# Triple_Micro_Shield.net
KiCad netlist of a schematic drawn in EAGLE
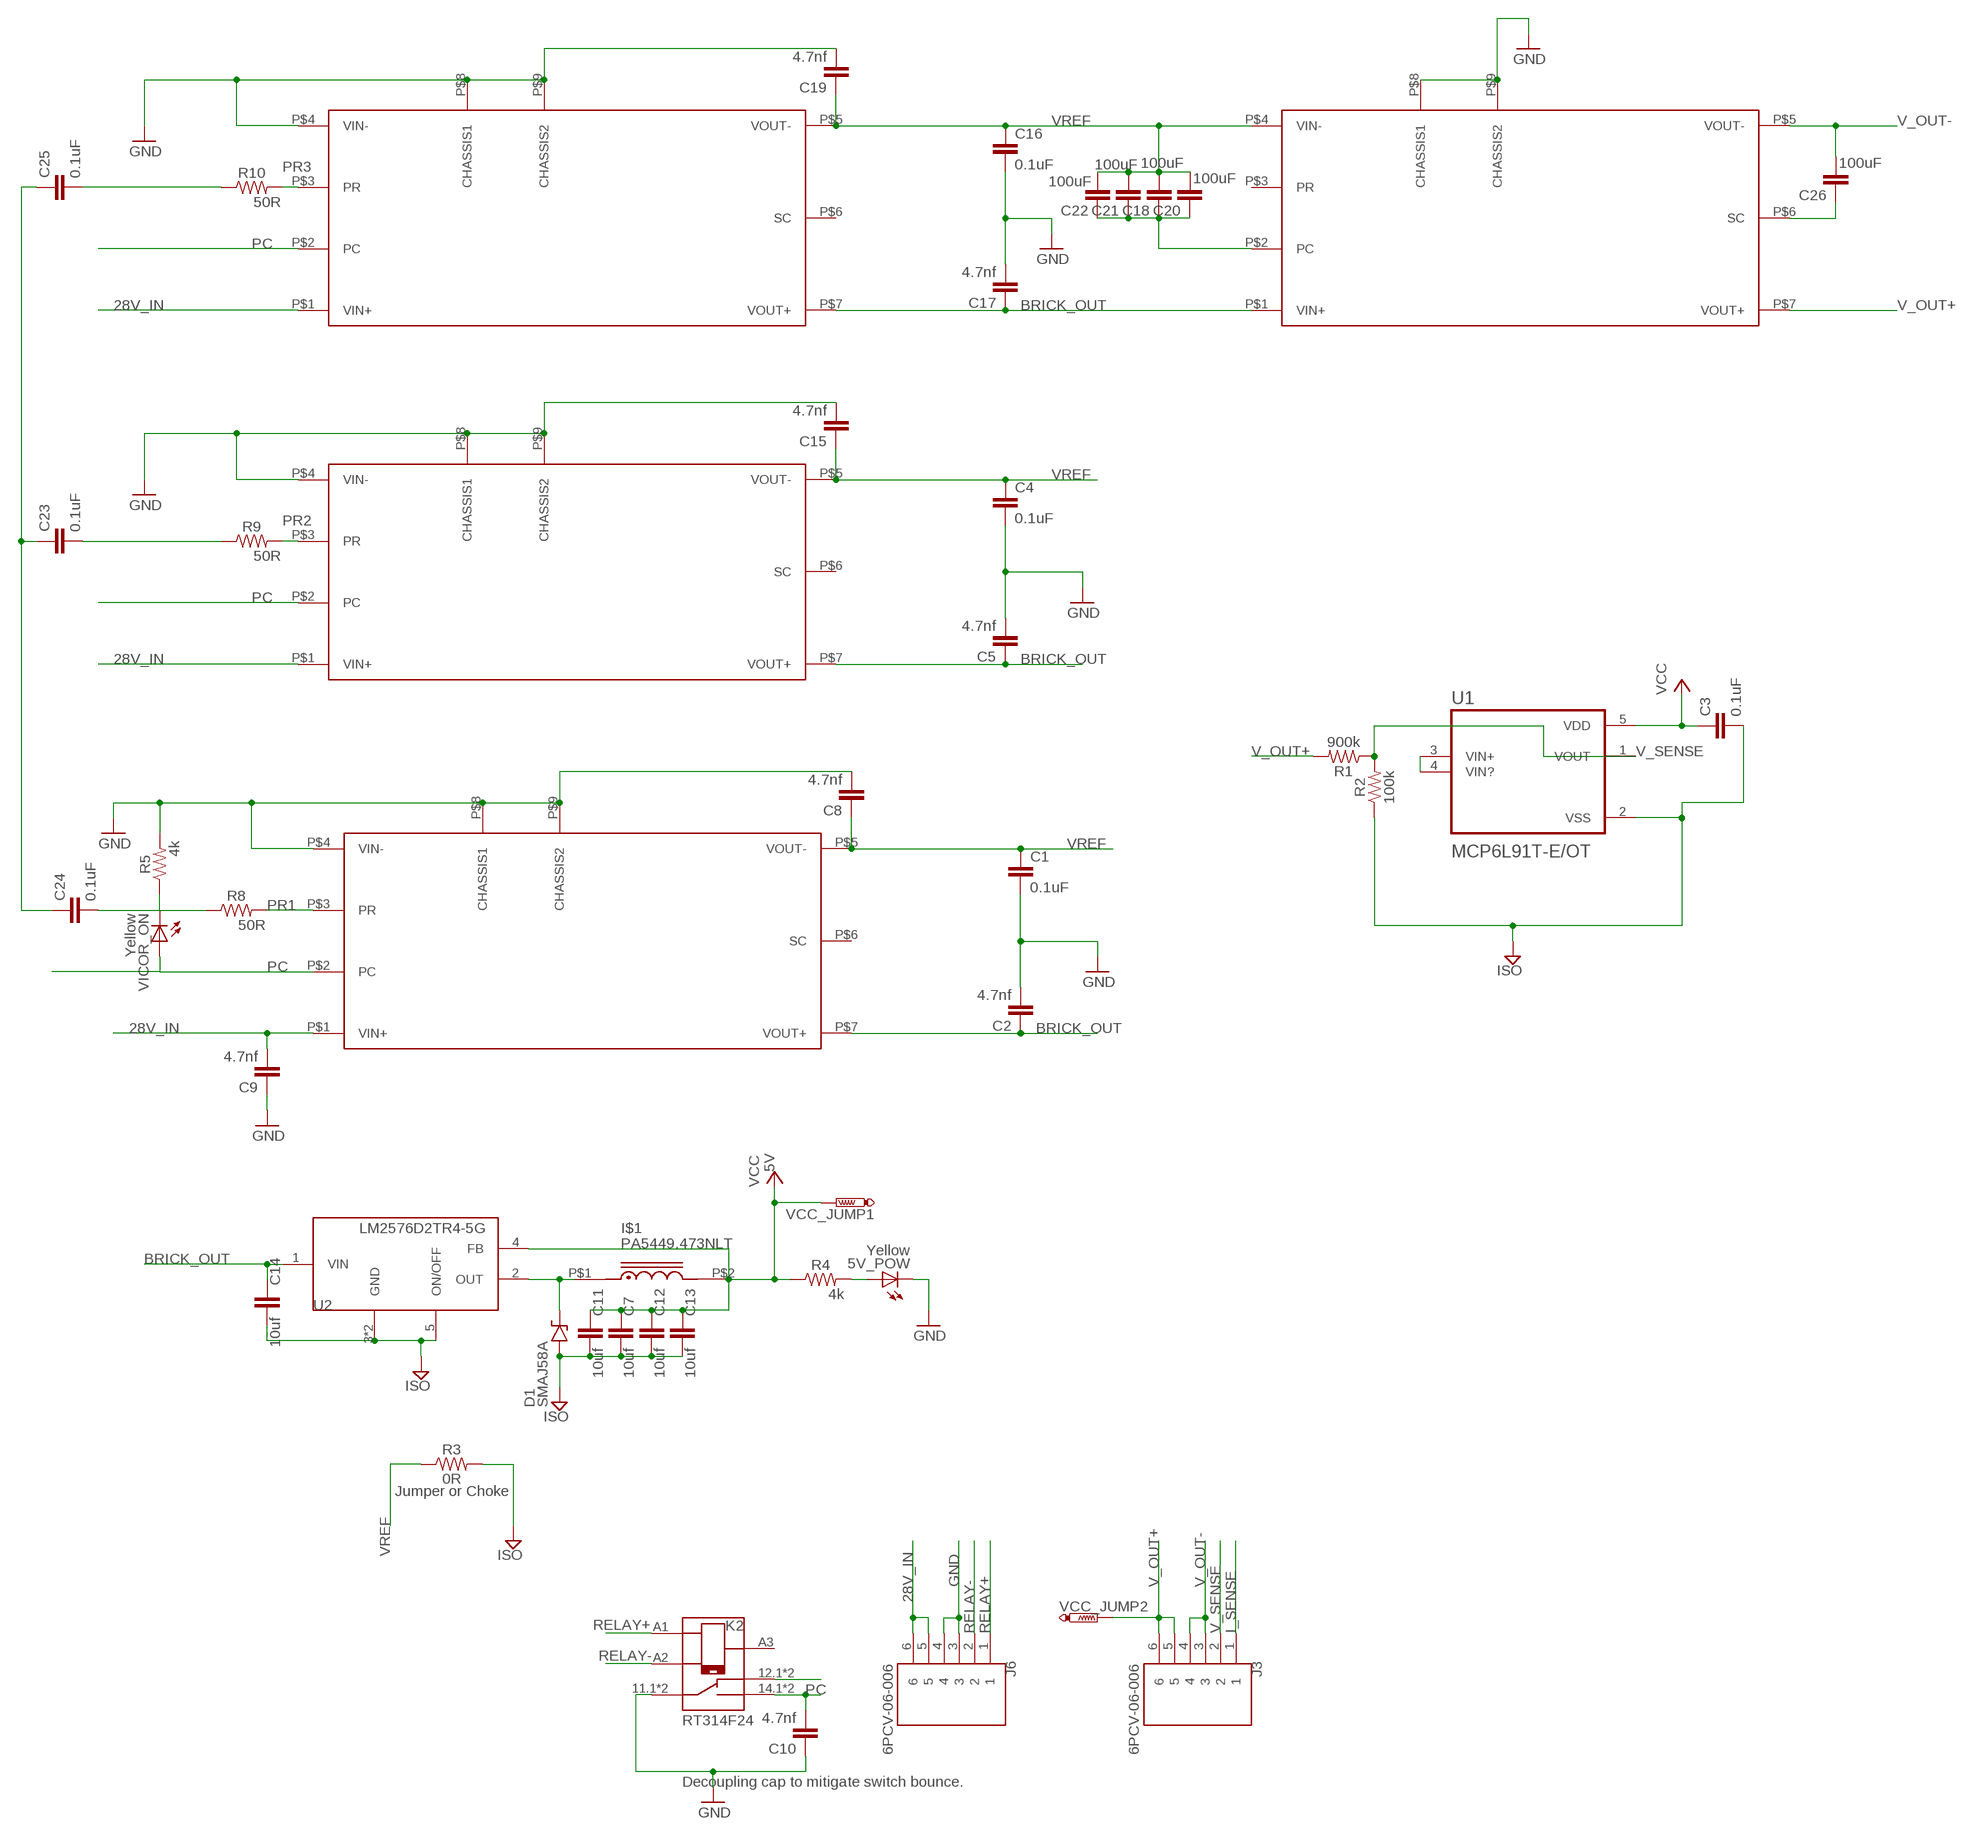
[diagram p0: schematic, sheet 1]

(export (version "E")
  (design (tool "Eeschema 10.0.6"))
  (components
    (comp (ref "5V_POW")
      (value "Yellow")
      (footprint "eagle-import:CHIPLED_0805")
      (fields (field (name "PART_NUMBER") "KPT-2012YC"))
      (libsource (lib "eagle-import") (part "0044_KPT-2012YC"))
    )
    (comp (ref "C1")
      (value "0.1uF")
      (footprint "eagle-import:0603")
      (libsource (lib "eagle-import") (part "5.6NF/5600PF_0603_50V_5%"))
    )
    (comp (ref "C2")
      (value "4.7nf")
      (footprint "eagle-import:0603")
      (libsource (lib "eagle-import") (part "5.6NF/5600PF_0603_50V_5%"))
    )
    (comp (ref "C3")
      (value "0.1uF")
      (footprint "eagle-import:0603")
      (libsource (lib "eagle-import") (part "5.6NF/5600PF_0603_50V_5%"))
    )
    (comp (ref "C4")
      (value "0.1uF")
      (footprint "eagle-import:0603")
      (libsource (lib "eagle-import") (part "5.6NF/5600PF_0603_50V_5%"))
    )
    (comp (ref "C5")
      (value "4.7nf")
      (footprint "eagle-import:0603")
      (libsource (lib "eagle-import") (part "5.6NF/5600PF_0603_50V_5%"))
    )
    (comp (ref "C7")
      (value "10uf")
      (footprint "eagle-import:0805")
      (libsource (lib "eagle-import") (part "39NF-0805-50V-10%"))
    )
    (comp (ref "C8")
      (value "4.7nf")
      (footprint "eagle-import:0603")
      (libsource (lib "eagle-import") (part "5.6NF/5600PF_0603_50V_5%"))
    )
    (comp (ref "C9")
      (value "4.7nf")
      (footprint "eagle-import:0603")
      (libsource (lib "eagle-import") (part "5.6NF/5600PF_0603_50V_5%"))
    )
    (comp (ref "C10")
      (value "4.7nf")
      (footprint "eagle-import:0603")
      (libsource (lib "eagle-import") (part "5.6NF/5600PF_0603_50V_5%"))
    )
    (comp (ref "C11")
      (value "10uf")
      (footprint "eagle-import:0805")
      (libsource (lib "eagle-import") (part "39NF-0805-50V-10%"))
    )
    (comp (ref "C12")
      (value "10uf")
      (footprint "eagle-import:0805")
      (libsource (lib "eagle-import") (part "39NF-0805-50V-10%"))
    )
    (comp (ref "C13")
      (value "10uf")
      (footprint "eagle-import:0805")
      (libsource (lib "eagle-import") (part "39NF-0805-50V-10%"))
    )
    (comp (ref "C14")
      (value "10uf")
      (footprint "eagle-import:0805")
      (libsource (lib "eagle-import") (part "39NF-0805-50V-10%"))
    )
    (comp (ref "C15")
      (value "4.7nf")
      (footprint "eagle-import:0603")
      (libsource (lib "eagle-import") (part "5.6NF/5600PF_0603_50V_5%"))
    )
    (comp (ref "C16")
      (value "0.1uF")
      (footprint "eagle-import:0603")
      (libsource (lib "eagle-import") (part "5.6NF/5600PF_0603_50V_5%"))
    )
    (comp (ref "C17")
      (value "4.7nf")
      (footprint "eagle-import:0603")
      (libsource (lib "eagle-import") (part "5.6NF/5600PF_0603_50V_5%"))
    )
    (comp (ref "C18")
      (value "100uF")
      (footprint "eagle-import:0603")
      (libsource (lib "eagle-import") (part "5.6NF/5600PF_0603_50V_5%"))
    )
    (comp (ref "C19")
      (value "4.7nf")
      (footprint "eagle-import:0603")
      (libsource (lib "eagle-import") (part "5.6NF/5600PF_0603_50V_5%"))
    )
    (comp (ref "C20")
      (value "100uF")
      (footprint "eagle-import:0603")
      (libsource (lib "eagle-import") (part "5.6NF/5600PF_0603_50V_5%"))
    )
    (comp (ref "C21")
      (value "100uF")
      (footprint "eagle-import:0603")
      (libsource (lib "eagle-import") (part "5.6NF/5600PF_0603_50V_5%"))
    )
    (comp (ref "C22")
      (value "100uF")
      (footprint "eagle-import:0603")
      (libsource (lib "eagle-import") (part "5.6NF/5600PF_0603_50V_5%"))
    )
    (comp (ref "C23")
      (value "0.1uF")
      (footprint "eagle-import:0603")
      (libsource (lib "eagle-import") (part "5.6NF/5600PF_0603_50V_5%"))
    )
    (comp (ref "C24")
      (value "0.1uF")
      (footprint "eagle-import:0603")
      (libsource (lib "eagle-import") (part "5.6NF/5600PF_0603_50V_5%"))
    )
    (comp (ref "C25")
      (value "0.1uF")
      (footprint "eagle-import:0603")
      (libsource (lib "eagle-import") (part "5.6NF/5600PF_0603_50V_5%"))
    )
    (comp (ref "C26")
      (value "100uF")
      (footprint "eagle-import:0603")
      (libsource (lib "eagle-import") (part "5.6NF/5600PF_0603_50V_5%"))
    )
    (comp (ref "D1")
      (value "SMAJ58A")
      (footprint "eagle-import:SMA")
      (fields (field (name "MF") "Littelfuse Inc."))
      (libsource (lib "eagle-import") (part "SMAJ58A"))
    )
    (comp (ref "I$1")
      (value "PA5449.473NLT")
      (footprint "eagle-import:IND_TYS4020470M-10")
      (libsource (lib "eagle-import") (part "PULSE_ELECTRONICS_INDUCTOR"))
    )
    (comp (ref "J3")
      (value "6PCV-06-006")
      (footprint "eagle-import:TE_9-1437652-5")
      (fields (field (name "COMMENT") "9-1437652-5") (field (name "MF") "TE Connectivity"))
      (libsource (lib "eagle-import") (part "6PCV-06-006"))
    )
    (comp (ref "J6")
      (value "6PCV-06-006")
      (footprint "eagle-import:TE_9-1437652-5")
      (fields (field (name "COMMENT") "9-1437652-5") (field (name "MF") "TE Connectivity"))
      (libsource (lib "eagle-import") (part "6PCV-06-006"))
    )
    (comp (ref "K2")
      (value "RT314F24")
      (footprint "eagle-import:TE_8-1393239-8")
      (fields (field (name "COMMENT") "8-1393239-8") (field (name "MF") "TE Connectivity"))
      (libsource (lib "eagle-import") (part "8-1393239-8"))
    )
    (comp (ref "R1")
      (value "900k")
      (footprint "eagle-import:0603")
      (libsource (lib "eagle-import") (part "1.8MOHM"))
    )
    (comp (ref "R2")
      (value "100k")
      (footprint "eagle-import:0603")
      (libsource (lib "eagle-import") (part "1.8MOHM"))
    )
    (comp (ref "R3")
      (value "0R")
      (footprint "eagle-import:0603")
      (libsource (lib "eagle-import") (part "1.8MOHM"))
    )
    (comp (ref "R4")
      (value "4k")
      (footprint "eagle-import:0603")
      (libsource (lib "eagle-import") (part "1.8MOHM"))
    )
    (comp (ref "R5")
      (value "4k")
      (footprint "eagle-import:0603")
      (libsource (lib "eagle-import") (part "1.8MOHM"))
    )
    (comp (ref "R8")
      (value "50R")
      (footprint "eagle-import:0603")
      (libsource (lib "eagle-import") (part "1.8MOHM"))
    )
    (comp (ref "R9")
      (value "50R")
      (footprint "eagle-import:0603")
      (libsource (lib "eagle-import") (part "1.8MOHM"))
    )
    (comp (ref "R10")
      (value "50R")
      (footprint "eagle-import:0603")
      (libsource (lib "eagle-import") (part "1.8MOHM"))
    )
    (comp (ref "U$2")
      (value "VICOR_MINI_BRICK_VICORMINIBRICK")
      (footprint "eagle-import:VICOR_MINI_BRICK_MINIBRICK")
      (libsource (lib "eagle-import") (part "VICOR_MINI_BRICK_VICORMINIBRICK"))
    )
    (comp (ref "U$3")
      (value "VICOR_MINI_BRICK_VICORMINIBRICK")
      (footprint "eagle-import:VICOR_MINI_BRICK_MINIBRICK")
      (libsource (lib "eagle-import") (part "VICOR_MINI_BRICK_VICORMINIBRICK"))
    )
    (comp (ref "U$4")
      (value "VICOR_MINI_BRICK_VICORMINIBRICK")
      (footprint "eagle-import:VICOR_MINI_BRICK_MINIBRICK")
      (libsource (lib "eagle-import") (part "VICOR_MINI_BRICK_VICORMINIBRICK"))
    )
    (comp (ref "U$5")
      (value "VICOR_MINI_BRICK_VICORMINIBRICK")
      (footprint "eagle-import:VICOR_MINI_BRICK_MINIBRICK")
      (libsource (lib "eagle-import") (part "VICOR_MINI_BRICK_VICORMINIBRICK"))
    )
    (comp (ref "U1")
      (value "MCP6L91T-E/OT")
      (footprint "eagle-import:SOT95P270X145-5N")
      (fields (field (name "MF") "Microchip Technology"))
      (libsource (lib "eagle-import") (part "MCP6L91T-E/OT"))
    )
    (comp (ref "U2")
      (value "LM2576D2TR4-5G")
      (footprint "eagle-import:D2PAK-5")
      (fields (field (name "MF") "ON Semiconductor"))
      (libsource (lib "eagle-import") (part "LM2576D2TR4-5G"))
    )
    (comp (ref "VCC_JUMP1")
      (value "PTR1PAD1-13")
      (footprint "eagle-import:P1-13")
      (libsource (lib "eagle-import") (part "PTR1PAD1-13"))
    )
    (comp (ref "VCC_JUMP2")
      (value "PTR1PAD1-13")
      (footprint "eagle-import:P1-13")
      (libsource (lib "eagle-import") (part "PTR1PAD1-13"))
    )
    (comp (ref "VICOR_ON")
      (value "Yellow")
      (footprint "eagle-import:CHIPLED_0805")
      (fields (field (name "PART_NUMBER") "KPT-2012YC"))
      (libsource (lib "eagle-import") (part "0044_KPT-2012YC"))
    )
  )
  (nets
    (net (code "1") (name "/28V_IN") (class "Default")
      (node (ref "C9") (pin "2") (pinfunction "2_2") (pintype "passive"))
      (node (ref "J6") (pin "5") (pinfunction "5_5") (pintype "passive"))
      (node (ref "J6") (pin "6") (pinfunction "6_6") (pintype "passive"))
      (node (ref "U$2") (pin "P$1") (pinfunction "VIN+_P$1") (pintype "bidirectional"))
      (node (ref "U$3") (pin "P$1") (pinfunction "VIN+_P$1") (pintype "bidirectional"))
      (node (ref "U$4") (pin "P$1") (pinfunction "VIN+_P$1") (pintype "bidirectional"))
    )
    (net (code "2") (name "/BRICK_OUT") (class "Default")
      (node (ref "C14") (pin "1") (pinfunction "1_1") (pintype "passive"))
      (node (ref "C17") (pin "1") (pinfunction "1_1") (pintype "passive"))
      (node (ref "C2") (pin "1") (pinfunction "1_1") (pintype "passive"))
      (node (ref "C5") (pin "1") (pinfunction "1_1") (pintype "passive"))
      (node (ref "U$2") (pin "P$7") (pinfunction "VOUT+_P$7") (pintype "bidirectional"))
      (node (ref "U$3") (pin "P$7") (pinfunction "VOUT+_P$7") (pintype "bidirectional"))
      (node (ref "U$4") (pin "P$7") (pinfunction "VOUT+_P$7") (pintype "bidirectional"))
      (node (ref "U$5") (pin "P$1") (pinfunction "VIN+_P$1") (pintype "bidirectional"))
      (node (ref "U2") (pin "1") (pinfunction "VIN_1") (pintype "input"))
    )
    (net (code "3") (name "/I_SENSE") (class "Default")
      (node (ref "J3") (pin "1") (pinfunction "1_1") (pintype "passive"))
    )
    (net (code "4") (name "/PC") (class "Default")
      (node (ref "C10") (pin "2") (pinfunction "2_2") (pintype "passive"))
      (node (ref "K2") (pin "14.1") (pinfunction "14_14.1") (pintype "passive"))
      (node (ref "K2") (pin "14.2") (pinfunction "14_14.2") (pintype "passive"))
      (node (ref "U$2") (pin "P$2") (pinfunction "PC_P$2") (pintype "bidirectional"))
      (node (ref "U$3") (pin "P$2") (pinfunction "PC_P$2") (pintype "bidirectional"))
      (node (ref "U$4") (pin "P$2") (pinfunction "PC_P$2") (pintype "bidirectional"))
      (node (ref "VICOR_ON") (pin "A") (pinfunction "A_A") (pintype "passive"))
    )
    (net (code "5") (name "/PR1") (class "Default")
      (node (ref "R8") (pin "2") (pinfunction "2_2") (pintype "passive"))
      (node (ref "U$2") (pin "P$3") (pinfunction "PR_P$3") (pintype "bidirectional"))
    )
    (net (code "6") (name "/PR2") (class "Default")
      (node (ref "R9") (pin "2") (pinfunction "2_2") (pintype "passive"))
      (node (ref "U$3") (pin "P$3") (pinfunction "PR_P$3") (pintype "bidirectional"))
    )
    (net (code "7") (name "/PR3") (class "Default")
      (node (ref "R10") (pin "2") (pinfunction "2_2") (pintype "passive"))
      (node (ref "U$4") (pin "P$3") (pinfunction "PR_P$3") (pintype "bidirectional"))
    )
    (net (code "8") (name "/RELAY+") (class "Default")
      (node (ref "J6") (pin "1") (pinfunction "1_1") (pintype "passive"))
      (node (ref "K2") (pin "A1") (pinfunction "A1_A1") (pintype "passive"))
    )
    (net (code "9") (name "/RELAY-") (class "Default")
      (node (ref "J6") (pin "2") (pinfunction "2_2") (pintype "passive"))
      (node (ref "K2") (pin "A2") (pinfunction "A2_A2") (pintype "passive"))
    )
    (net (code "10") (name "/VREF") (class "Default")
      (node (ref "C1") (pin "1") (pinfunction "1_1") (pintype "passive"))
      (node (ref "C15") (pin "1") (pinfunction "1_1") (pintype "passive"))
      (node (ref "C16") (pin "1") (pinfunction "1_1") (pintype "passive"))
      (node (ref "C18") (pin "2") (pinfunction "2_2") (pintype "passive"))
      (node (ref "C19") (pin "1") (pinfunction "1_1") (pintype "passive"))
      (node (ref "C20") (pin "2") (pinfunction "2_2") (pintype "passive"))
      (node (ref "C21") (pin "2") (pinfunction "2_2") (pintype "passive"))
      (node (ref "C22") (pin "2") (pinfunction "2_2") (pintype "passive"))
      (node (ref "C4") (pin "1") (pinfunction "1_1") (pintype "passive"))
      (node (ref "C8") (pin "1") (pinfunction "1_1") (pintype "passive"))
      (node (ref "R3") (pin "1") (pinfunction "1_1") (pintype "passive"))
      (node (ref "U$2") (pin "P$5") (pinfunction "VOUT-_P$5") (pintype "bidirectional"))
      (node (ref "U$3") (pin "P$5") (pinfunction "VOUT-_P$5") (pintype "bidirectional"))
      (node (ref "U$4") (pin "P$5") (pinfunction "VOUT-_P$5") (pintype "bidirectional"))
      (node (ref "U$5") (pin "P$4") (pinfunction "VIN-_P$4") (pintype "bidirectional"))
    )
    (net (code "11") (name "/V_OUT+") (class "Default")
      (node (ref "J3") (pin "5") (pinfunction "5_5") (pintype "passive"))
      (node (ref "J3") (pin "6") (pinfunction "6_6") (pintype "passive"))
      (node (ref "R1") (pin "2") (pinfunction "2_2") (pintype "passive"))
      (node (ref "U$5") (pin "P$7") (pinfunction "VOUT+_P$7") (pintype "bidirectional"))
      (node (ref "VCC_JUMP2") (pin "TP") (pinfunction "TP_TP") (pintype "input"))
    )
    (net (code "12") (name "/V_OUT-") (class "Default")
      (node (ref "C26") (pin "2") (pinfunction "2_2") (pintype "passive"))
      (node (ref "J3") (pin "3") (pinfunction "3_3") (pintype "passive"))
      (node (ref "J3") (pin "4") (pinfunction "4_4") (pintype "passive"))
      (node (ref "U$5") (pin "P$5") (pinfunction "VOUT-_P$5") (pintype "bidirectional"))
    )
    (net (code "13") (name "/V_SENSE") (class "Default")
      (node (ref "J3") (pin "2") (pinfunction "2_2") (pintype "passive"))
      (node (ref "U1") (pin "3") (pinfunction "VIN+_3") (pintype "input"))
      (node (ref "U1") (pin "4") (pinfunction "VIN?_4") (pintype "input"))
    )
    (net (code "14") (name "GND") (class "Default")
      (node (ref "5V_POW") (pin "C") (pinfunction "C_C") (pintype "passive"))
      (node (ref "C1") (pin "2") (pinfunction "2_2") (pintype "passive"))
      (node (ref "C10") (pin "1") (pinfunction "1_1") (pintype "passive"))
      (node (ref "C15") (pin "2") (pinfunction "2_2") (pintype "passive"))
      (node (ref "C16") (pin "2") (pinfunction "2_2") (pintype "passive"))
      (node (ref "C17") (pin "2") (pinfunction "2_2") (pintype "passive"))
      (node (ref "C19") (pin "2") (pinfunction "2_2") (pintype "passive"))
      (node (ref "C2") (pin "2") (pinfunction "2_2") (pintype "passive"))
      (node (ref "C4") (pin "2") (pinfunction "2_2") (pintype "passive"))
      (node (ref "C5") (pin "2") (pinfunction "2_2") (pintype "passive"))
      (node (ref "C8") (pin "2") (pinfunction "2_2") (pintype "passive"))
      (node (ref "C9") (pin "1") (pinfunction "1_1") (pintype "passive"))
      (node (ref "J6") (pin "3") (pinfunction "3_3") (pintype "passive"))
      (node (ref "J6") (pin "4") (pinfunction "4_4") (pintype "passive"))
      (node (ref "K2") (pin "11.1") (pinfunction "11_11.1") (pintype "passive"))
      (node (ref "K2") (pin "11.2") (pinfunction "11_11.2") (pintype "passive"))
      (node (ref "R5") (pin "2") (pinfunction "2_2") (pintype "passive"))
      (node (ref "U$2") (pin "P$4") (pinfunction "VIN-_P$4") (pintype "bidirectional"))
      (node (ref "U$2") (pin "P$8") (pinfunction "CHASSIS1_P$8") (pintype "bidirectional"))
      (node (ref "U$2") (pin "P$9") (pinfunction "CHASSIS2_P$9") (pintype "bidirectional"))
      (node (ref "U$3") (pin "P$4") (pinfunction "VIN-_P$4") (pintype "bidirectional"))
      (node (ref "U$3") (pin "P$8") (pinfunction "CHASSIS1_P$8") (pintype "bidirectional"))
      (node (ref "U$3") (pin "P$9") (pinfunction "CHASSIS2_P$9") (pintype "bidirectional"))
      (node (ref "U$4") (pin "P$4") (pinfunction "VIN-_P$4") (pintype "bidirectional"))
      (node (ref "U$4") (pin "P$8") (pinfunction "CHASSIS1_P$8") (pintype "bidirectional"))
      (node (ref "U$4") (pin "P$9") (pinfunction "CHASSIS2_P$9") (pintype "bidirectional"))
      (node (ref "U$5") (pin "P$8") (pinfunction "CHASSIS1_P$8") (pintype "bidirectional"))
      (node (ref "U$5") (pin "P$9") (pinfunction "CHASSIS2_P$9") (pintype "bidirectional"))
    )
    (net (code "15") (name "ISO") (class "Default")
      (node (ref "C11") (pin "2") (pinfunction "2_2") (pintype "passive"))
      (node (ref "C12") (pin "2") (pinfunction "2_2") (pintype "passive"))
      (node (ref "C13") (pin "2") (pinfunction "2_2") (pintype "passive"))
      (node (ref "C14") (pin "2") (pinfunction "2_2") (pintype "passive"))
      (node (ref "C3") (pin "2") (pinfunction "2_2") (pintype "passive"))
      (node (ref "C7") (pin "2") (pinfunction "2_2") (pintype "passive"))
      (node (ref "D1") (pin "A") (pinfunction "A_A") (pintype "passive"))
      (node (ref "R2") (pin "1") (pinfunction "1_1") (pintype "passive"))
      (node (ref "R3") (pin "2") (pinfunction "2_2") (pintype "passive"))
      (node (ref "U1") (pin "2") (pinfunction "VSS_2") (pintype "power_in"))
      (node (ref "U2") (pin "3") (pinfunction "GND_3") (pintype "passive"))
      (node (ref "U2") (pin "5") (pinfunction "ON/OFF_5") (pintype "input"))
      (node (ref "U2") (pin "6") (pinfunction "GND_6") (pintype "passive"))
    )
    (net (code "16") (name "Net-(5V_POW-PadA)") (class "Default")
      (node (ref "5V_POW") (pin "A") (pinfunction "A_A") (pintype "passive"))
      (node (ref "R4") (pin "2") (pinfunction "2_2") (pintype "passive"))
    )
    (net (code "17") (name "Net-(C23-Pad1)") (class "Default")
      (node (ref "C23") (pin "1") (pinfunction "1_1") (pintype "passive"))
      (node (ref "C24") (pin "1") (pinfunction "1_1") (pintype "passive"))
      (node (ref "C25") (pin "1") (pinfunction "1_1") (pintype "passive"))
    )
    (net (code "18") (name "Net-(C23-Pad2)") (class "Default")
      (node (ref "C23") (pin "2") (pinfunction "2_2") (pintype "passive"))
      (node (ref "R9") (pin "1") (pinfunction "1_1") (pintype "passive"))
    )
    (net (code "19") (name "Net-(C24-Pad2)") (class "Default")
      (node (ref "C24") (pin "2") (pinfunction "2_2") (pintype "passive"))
      (node (ref "R8") (pin "1") (pinfunction "1_1") (pintype "passive"))
    )
    (net (code "20") (name "Net-(C25-Pad2)") (class "Default")
      (node (ref "C25") (pin "2") (pinfunction "2_2") (pintype "passive"))
      (node (ref "R10") (pin "1") (pinfunction "1_1") (pintype "passive"))
    )
    (net (code "21") (name "Net-(I$1-1)") (class "Default")
      (node (ref "D1") (pin "C") (pinfunction "C_C") (pintype "passive"))
      (node (ref "I$1") (pin "P$1") (pinfunction "1_P$1") (pintype "passive"))
      (node (ref "U2") (pin "2") (pinfunction "OUT_2") (pintype "output"))
    )
    (net (code "22") (name "Net-(K2-12-Pad12.1)") (class "Default")
      (node (ref "K2") (pin "12.1") (pinfunction "12_12.1") (pintype "passive"))
      (node (ref "K2") (pin "12.2") (pinfunction "12_12.2") (pintype "passive"))
    )
    (net (code "23") (name "Net-(R5-Pad1)") (class "Default")
      (node (ref "R5") (pin "1") (pinfunction "1_1") (pintype "passive"))
      (node (ref "VICOR_ON") (pin "C") (pinfunction "C_C") (pintype "passive"))
    )
    (net (code "24") (name "Net-(U$5-PC)") (class "Default")
      (node (ref "C18") (pin "1") (pinfunction "1_1") (pintype "passive"))
      (node (ref "C20") (pin "1") (pinfunction "1_1") (pintype "passive"))
      (node (ref "C21") (pin "1") (pinfunction "1_1") (pintype "passive"))
      (node (ref "C22") (pin "1") (pinfunction "1_1") (pintype "passive"))
      (node (ref "U$5") (pin "P$2") (pinfunction "PC_P$2") (pintype "bidirectional"))
    )
    (net (code "25") (name "Net-(U$5-SC)") (class "Default")
      (node (ref "C26") (pin "1") (pinfunction "1_1") (pintype "passive"))
      (node (ref "U$5") (pin "P$6") (pinfunction "SC_P$6") (pintype "bidirectional"))
    )
    (net (code "26") (name "Net-(U1-VOUT)") (class "Default")
      (node (ref "R1") (pin "1") (pinfunction "1_1") (pintype "passive"))
      (node (ref "R2") (pin "2") (pinfunction "2_2") (pintype "passive"))
      (node (ref "U1") (pin "1") (pinfunction "VOUT_1") (pintype "output"))
    )
    (net (code "27") (name "VCC") (class "Default")
      (node (ref "C11") (pin "1") (pinfunction "1_1") (pintype "passive"))
      (node (ref "C12") (pin "1") (pinfunction "1_1") (pintype "passive"))
      (node (ref "C13") (pin "1") (pinfunction "1_1") (pintype "passive"))
      (node (ref "C3") (pin "1") (pinfunction "1_1") (pintype "passive"))
      (node (ref "C7") (pin "1") (pinfunction "1_1") (pintype "passive"))
      (node (ref "I$1") (pin "P$2") (pinfunction "2_P$2") (pintype "passive"))
      (node (ref "R4") (pin "1") (pinfunction "1_1") (pintype "passive"))
      (node (ref "U1") (pin "5") (pinfunction "VDD_5") (pintype "power_in"))
      (node (ref "U2") (pin "4") (pinfunction "FB_4") (pintype "output"))
      (node (ref "VCC_JUMP1") (pin "TP") (pinfunction "TP_TP") (pintype "input"))
    )
    (net (code "28") (name "unconnected-(K2-PadA3)") (class "Default")
      (node (ref "K2") (pin "A3") (pinfunction "A3_A3") (pintype "passive"))
    )
    (net (code "29") (name "unconnected-(U$2-SC-PadP$6)") (class "Default")
      (node (ref "U$2") (pin "P$6") (pinfunction "SC_P$6") (pintype "bidirectional"))
    )
    (net (code "30") (name "unconnected-(U$3-SC-PadP$6)") (class "Default")
      (node (ref "U$3") (pin "P$6") (pinfunction "SC_P$6") (pintype "bidirectional"))
    )
    (net (code "31") (name "unconnected-(U$4-SC-PadP$6)") (class "Default")
      (node (ref "U$4") (pin "P$6") (pinfunction "SC_P$6") (pintype "bidirectional"))
    )
    (net (code "32") (name "unconnected-(U$5-PR-PadP$3)") (class "Default")
      (node (ref "U$5") (pin "P$3") (pinfunction "PR_P$3") (pintype "bidirectional"))
    )
  )
)
